# PPGColle.net
KiCad netlist of a schematic drawn in Altium Designer
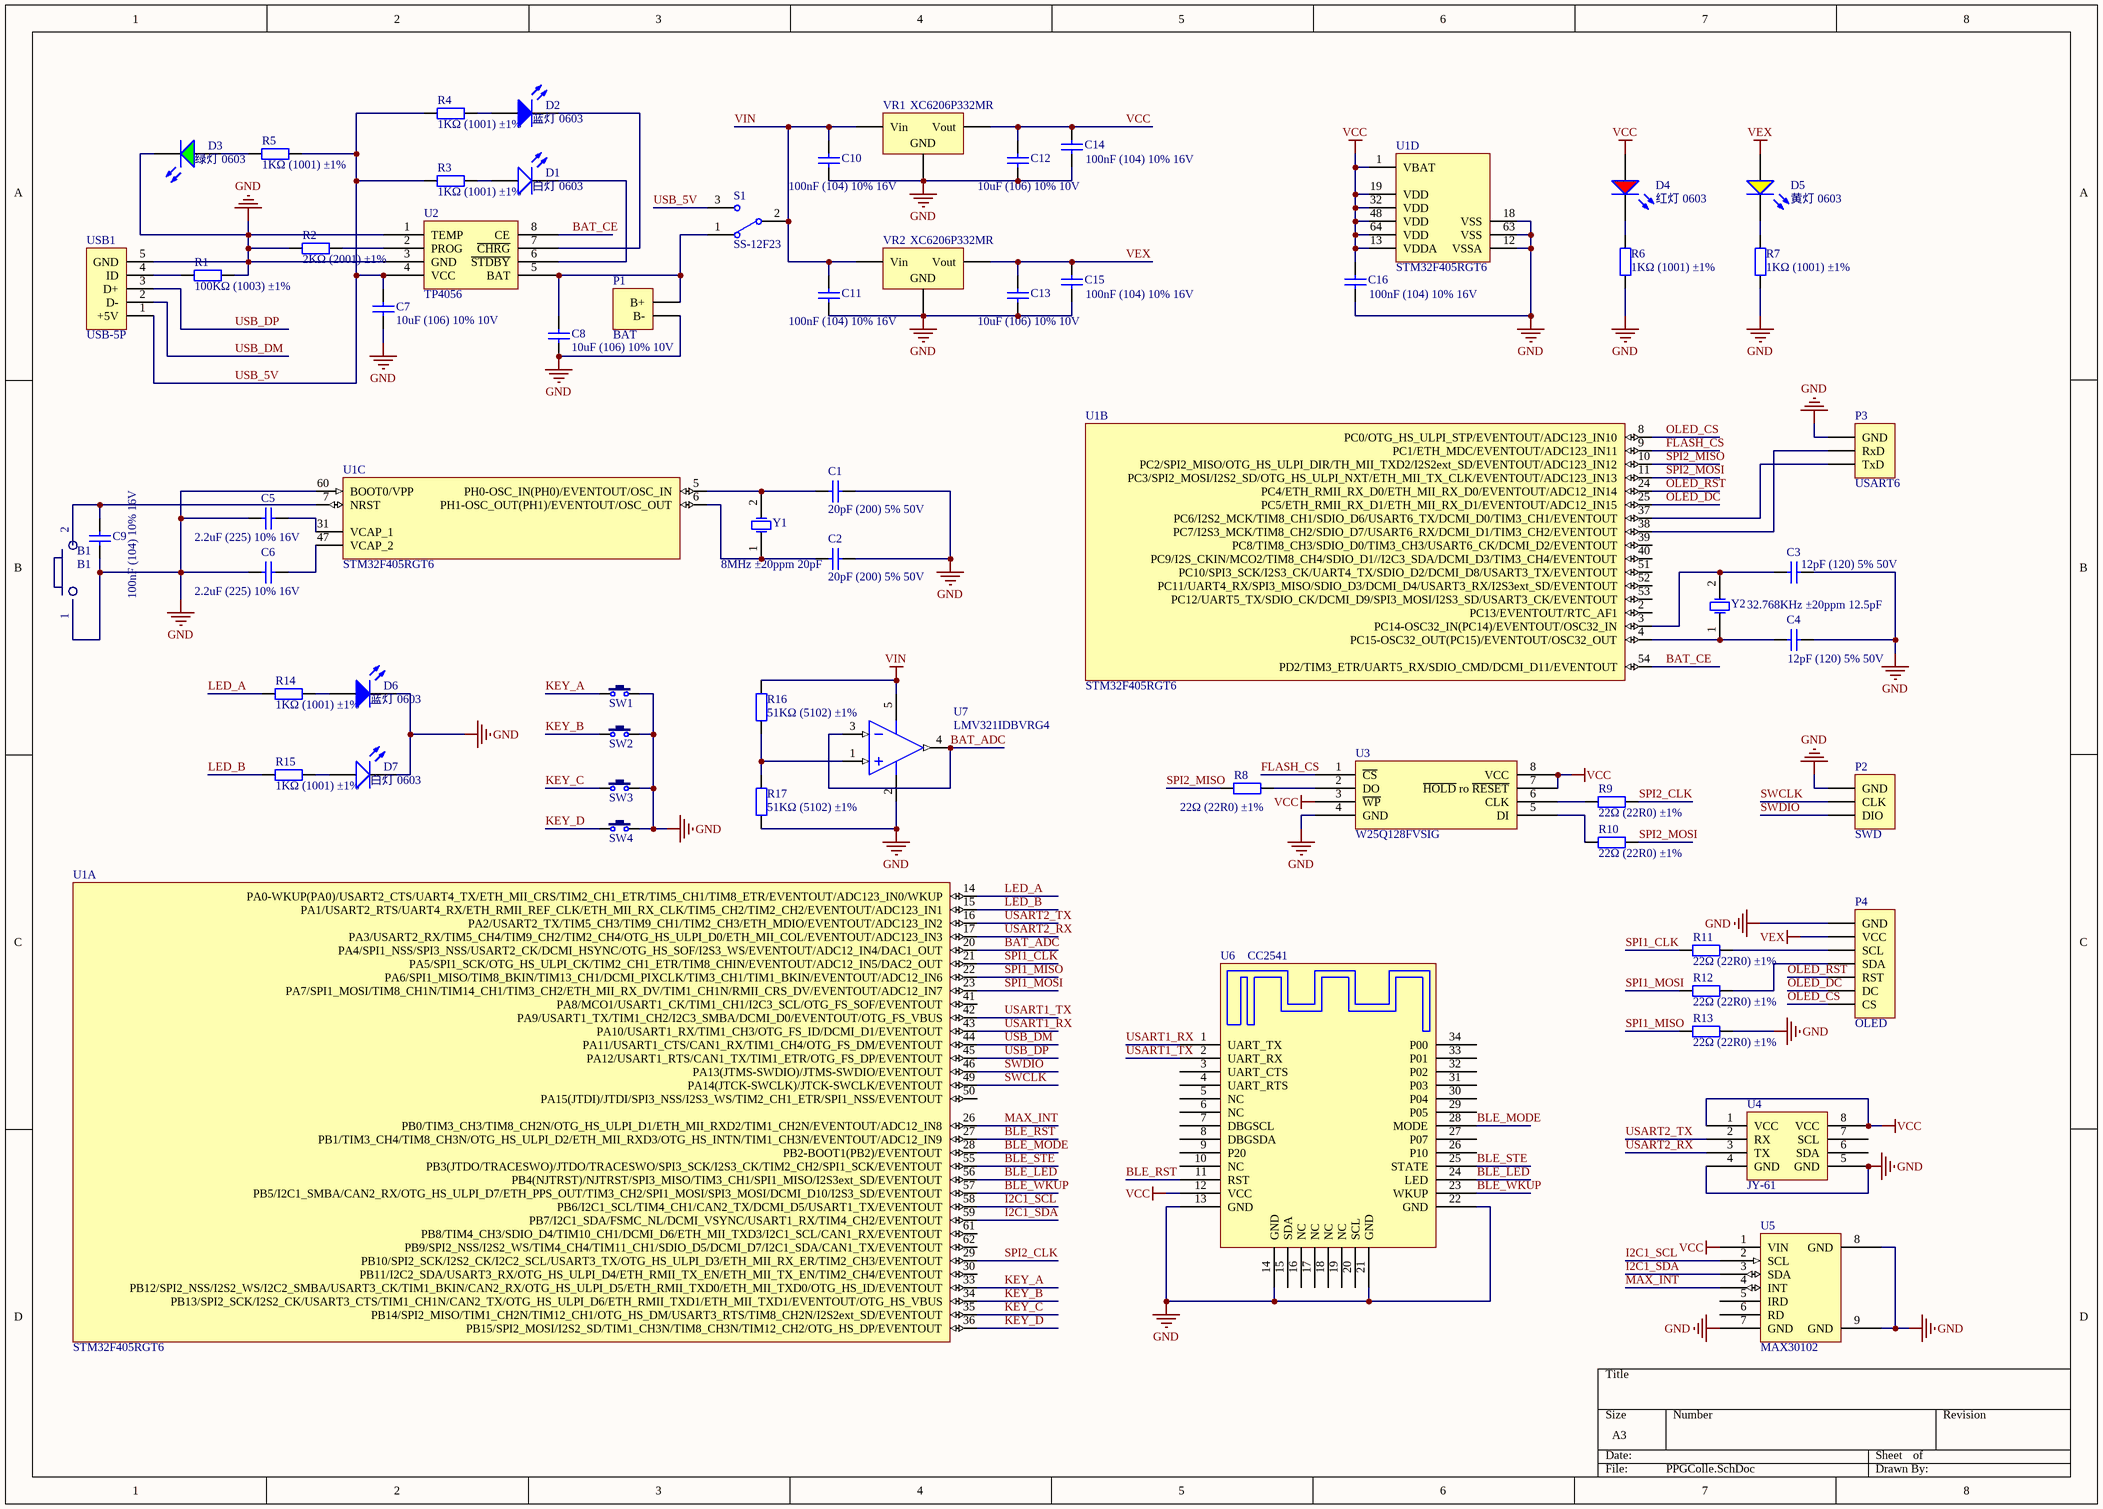
[diagram p0: PPGColle.SchDoc]

(export (version "E")
  (design (tool "Eeschema 10.0.6"))
  (components
    (comp (ref "B1")
      (value "B1")
      (footprint "MetalButton")
      (libsource (lib "MetalButton") (part "MetalButton"))
    )
    (comp (ref "C1")
      (value "20pF (200) 5% 50V")
      (footprint "0402_C")
      (description "贴片电容")
      (libsource (lib "Miscellaneous Devices LC") (part "0402 20pF (200) 5% 50V"))
    )
    (comp (ref "C2")
      (value "20pF (200) 5% 50V")
      (footprint "0402_C")
      (description "贴片电容")
      (libsource (lib "Miscellaneous Devices LC") (part "0402 20pF (200) 5% 50V"))
    )
    (comp (ref "C3")
      (value "12pF (120) 5% 50V")
      (footprint "0402_C")
      (description "贴片电容")
      (libsource (lib "Miscellaneous Devices LC") (part "0402 12pF (120) 5% 50V"))
    )
    (comp (ref "C4")
      (value "12pF (120) 5% 50V")
      (footprint "0402_C")
      (description "贴片电容")
      (libsource (lib "Miscellaneous Devices LC") (part "0402 12pF (120) 5% 50V"))
    )
    (comp (ref "C5")
      (value "2.2uF (225) 10% 16V")
      (footprint "0603_C")
      (description "贴片电容")
      (libsource (lib "Miscellaneous Devices LC") (part "0603 2.2uF (225) 10% 16V"))
    )
    (comp (ref "C6")
      (value "2.2uF (225) 10% 16V")
      (footprint "0603_C")
      (description "贴片电容")
      (libsource (lib "Miscellaneous Devices LC") (part "0603 2.2uF (225) 10% 16V"))
    )
    (comp (ref "C7")
      (value "10uF (106) 10% 10V")
      (footprint "0603_C")
      (description "贴片电容")
      (libsource (lib "Miscellaneous Devices LC") (part "0603 10uF (106) 10% 10V"))
    )
    (comp (ref "C8")
      (value "10uF (106) 10% 10V")
      (footprint "0603_C")
      (description "贴片电容")
      (libsource (lib "Miscellaneous Devices LC") (part "0603 10uF (106) 10% 10V"))
    )
    (comp (ref "C9")
      (value "100nF (104) 10% 16V")
      (footprint "0402_C")
      (description "贴片电容")
      (libsource (lib "Miscellaneous Devices LC") (part "0402 100nF (104) 10% 16V"))
    )
    (comp (ref "C10")
      (value "100nF (104) 10% 16V")
      (footprint "0402_C")
      (description "贴片电容")
      (libsource (lib "Miscellaneous Devices LC") (part "0402 100nF (104) 10% 16V"))
    )
    (comp (ref "C11")
      (value "100nF (104) 10% 16V")
      (footprint "0402_C")
      (description "贴片电容")
      (libsource (lib "Miscellaneous Devices LC") (part "0402 100nF (104) 10% 16V"))
    )
    (comp (ref "C12")
      (value "10uF (106) 10% 10V")
      (footprint "0603_C")
      (description "贴片电容")
      (libsource (lib "Miscellaneous Devices LC") (part "0603 10uF (106) 10% 10V"))
    )
    (comp (ref "C13")
      (value "10uF (106) 10% 10V")
      (footprint "0603_C")
      (description "贴片电容")
      (libsource (lib "Miscellaneous Devices LC") (part "0603 10uF (106) 10% 10V"))
    )
    (comp (ref "C14")
      (value "100nF (104) 10% 16V")
      (footprint "0402_C")
      (description "贴片电容")
      (libsource (lib "Miscellaneous Devices LC") (part "0402 100nF (104) 10% 16V"))
    )
    (comp (ref "C15")
      (value "100nF (104) 10% 16V")
      (footprint "0402_C")
      (description "贴片电容")
      (libsource (lib "Miscellaneous Devices LC") (part "0402 100nF (104) 10% 16V"))
    )
    (comp (ref "C16")
      (value "100nF (104) 10% 16V")
      (footprint "0402_C")
      (description "贴片电容")
      (libsource (lib "Miscellaneous Devices LC") (part "0402 100nF (104) 10% 16V"))
    )
    (comp (ref "D1")
      (value "白灯 0603")
      (footprint "0603_LED_S1")
      (description "发光二极管")
      (libsource (lib "Miscellaneous Devices LC") (part "0603 白灯"))
    )
    (comp (ref "D2")
      (value "蓝灯 0603")
      (footprint "0603_LED_S1")
      (description "发光二极管")
      (libsource (lib "Miscellaneous Devices LC") (part "0603 蓝灯"))
    )
    (comp (ref "D3")
      (value "绿灯 0603")
      (footprint "0603_LED_S1")
      (description "发光二极管")
      (libsource (lib "Miscellaneous Devices LC") (part "0603 绿灯"))
    )
    (comp (ref "D4")
      (value "红灯 0603")
      (footprint "0603_LED_S1")
      (description "发光二极管")
      (libsource (lib "Miscellaneous Devices LC") (part "0603 红灯"))
    )
    (comp (ref "D5")
      (value "黄灯 0603")
      (footprint "0603_LED_S1")
      (description "发光二极管")
      (libsource (lib "Miscellaneous Devices LC") (part "0603 黄灯"))
    )
    (comp (ref "D6")
      (value "蓝灯 0603")
      (footprint "0603_LED_S1")
      (description "发光二极管")
      (libsource (lib "Miscellaneous Devices LC") (part "0603 蓝灯"))
    )
    (comp (ref "D7")
      (value "白灯 0603")
      (footprint "0603_LED_S1")
      (description "发光二极管")
      (libsource (lib "Miscellaneous Devices LC") (part "0603 白灯"))
    )
    (comp (ref "P1")
      (value "BAT")
      (footprint "HDR1X2")
      (description "Header, 2-Pin")
      (fields (field (name "PUBLISHER") "Altium Limited"))
      (libsource (lib "Miscellaneous Connectors") (part "Header 2"))
    )
    (comp (ref "P2")
      (value "SWD")
      (footprint "HDR1X3H")
      (description "Header, 3-Pin, Right Angle")
      (fields (field (name "PUBLISHER") "Altium Limited"))
      (libsource (lib "Miscellaneous Connectors") (part "Header 3H"))
    )
    (comp (ref "P3")
      (value "USART6")
      (footprint "HDR1X3H")
      (description "Header, 3-Pin, Right Angle")
      (fields (field (name "PUBLISHER") "Altium Limited"))
      (libsource (lib "Miscellaneous Connectors") (part "Header 3H"))
    )
    (comp (ref "P4")
      (value "OLED")
      (footprint "HDR1X7")
      (description "Header, 7-Pin")
      (fields (field (name "PUBLISHER") "Altium Limited"))
      (libsource (lib "Miscellaneous Connectors") (part "Header 7"))
    )
    (comp (ref "R1")
      (value "100KΩ (1003) ±1%")
      (footprint "0402_R")
      (description "贴片电阻")
      (libsource (lib "Miscellaneous Devices LC") (part "0402 100KΩ (1003) 1%"))
    )
    (comp (ref "R2")
      (value "2KΩ (2001) ±1%")
      (footprint "0402_R")
      (description "贴片电阻")
      (libsource (lib "Miscellaneous Devices LC") (part "0402 2KΩ (2001) 1%"))
    )
    (comp (ref "R3")
      (value "1KΩ (1001) ±1%")
      (footprint "0402_R")
      (description "贴片电阻")
      (libsource (lib "Miscellaneous Devices LC") (part "0402 1KΩ (1001) 1%"))
    )
    (comp (ref "R4")
      (value "1KΩ (1001) ±1%")
      (footprint "0402_R")
      (description "贴片电阻")
      (libsource (lib "Miscellaneous Devices LC") (part "0402 1KΩ (1001) 1%"))
    )
    (comp (ref "R5")
      (value "1KΩ (1001) ±1%")
      (footprint "0402_R")
      (description "贴片电阻")
      (libsource (lib "Miscellaneous Devices LC") (part "0402 1KΩ (1001) 1%"))
    )
    (comp (ref "R6")
      (value "1KΩ (1001) ±1%")
      (footprint "0402_R")
      (description "贴片电阻")
      (libsource (lib "") (part "0402 1KΩ (1001) 1%_1"))
    )
    (comp (ref "R7")
      (value "1KΩ (1001) ±1%")
      (footprint "0402_R")
      (description "贴片电阻")
      (libsource (lib "") (part "0402 1KΩ (1001) 1%_1"))
    )
    (comp (ref "R8")
      (value "22Ω (22R0) ±1%")
      (footprint "0402_R")
      (description "贴片电阻")
      (libsource (lib "Miscellaneous Devices LC") (part "0402 22Ω (22R0) 1%"))
    )
    (comp (ref "R9")
      (value "22Ω (22R0) ±1%")
      (footprint "0402_R")
      (description "贴片电阻")
      (libsource (lib "Miscellaneous Devices LC") (part "0402 22Ω (22R0) 1%"))
    )
    (comp (ref "R10")
      (value "22Ω (22R0) ±1%")
      (footprint "0402_R")
      (description "贴片电阻")
      (libsource (lib "Miscellaneous Devices LC") (part "0402 22Ω (22R0) 1%"))
    )
    (comp (ref "R11")
      (value "22Ω (22R0) ±1%")
      (footprint "0402_R")
      (description "贴片电阻")
      (libsource (lib "Miscellaneous Devices LC") (part "0402 22Ω (22R0) 1%"))
    )
    (comp (ref "R12")
      (value "22Ω (22R0) ±1%")
      (footprint "0402_R")
      (description "贴片电阻")
      (libsource (lib "Miscellaneous Devices LC") (part "0402 22Ω (22R0) 1%"))
    )
    (comp (ref "R13")
      (value "22Ω (22R0) ±1%")
      (footprint "0402_R")
      (description "贴片电阻")
      (libsource (lib "Miscellaneous Devices LC") (part "0402 22Ω (22R0) 1%"))
    )
    (comp (ref "R14")
      (value "1KΩ (1001) ±1%")
      (footprint "0402_R")
      (description "贴片电阻")
      (libsource (lib "Miscellaneous Devices LC") (part "0402 1KΩ (1001) 1%"))
    )
    (comp (ref "R15")
      (value "1KΩ (1001) ±1%")
      (footprint "0402_R")
      (description "贴片电阻")
      (libsource (lib "Miscellaneous Devices LC") (part "0402 1KΩ (1001) 1%"))
    )
    (comp (ref "R16")
      (value "51KΩ (5102) ±1%")
      (footprint "0402_R")
      (description "贴片电阻")
      (libsource (lib "Miscellaneous Devices LC") (part "0402 51KΩ (5102) 1%"))
    )
    (comp (ref "R17")
      (value "51KΩ (5102) ±1%")
      (footprint "0402_R")
      (description "贴片电阻")
      (libsource (lib "Miscellaneous Devices LC") (part "0402 51KΩ (5102) 1%"))
    )
    (comp (ref "S1")
      (value "SS-12F23")
      (footprint "SS-12F23")
      (description "1路波动开关")
      (fields (field (name "版权归属") "源创客"))
      (libsource (lib "5.1   - 按键-开关") (part "SSW-1P"))
    )
    (comp (ref "SW1")
      (value "3x6x5")
      (footprint "TSW SMD-3*6*4.3")
      (description "3x6轻触开关")
      (fields (field (name "版权归属") "源创客"))
      (libsource (lib "5.1   - 按键-开关") (part "TSW 3x6"))
    )
    (comp (ref "SW2")
      (value "3x6x5")
      (footprint "TSW SMD-3*6*4.3")
      (description "3x6轻触开关")
      (fields (field (name "版权归属") "源创客"))
      (libsource (lib "5.1   - 按键-开关") (part "TSW 3x6"))
    )
    (comp (ref "SW3")
      (value "3x6x5")
      (footprint "TSW SMD-3*6*4.3")
      (description "3x6轻触开关")
      (fields (field (name "版权归属") "源创客"))
      (libsource (lib "5.1   - 按键-开关") (part "TSW 3x6"))
    )
    (comp (ref "SW4")
      (value "3x6x5")
      (footprint "TSW SMD-3*6*4.3")
      (description "3x6轻触开关")
      (fields (field (name "版权归属") "源创客"))
      (libsource (lib "5.1   - 按键-开关") (part "TSW 3x6"))
    )
    (comp (ref "U1")
      (value "STM32F405RGT6")
      (footprint "LQFP-64_10x10x05P")
      (description "ARM")
      (libsource (lib "Miscellaneous Devices LC") (part "STM32F405RGT6"))
    )
    (comp (ref "U2")
      (value "TP4056")
      (footprint "SOP-8_EP_150mil")
      (description "电池电源管理")
      (libsource (lib "Miscellaneous Devices LC") (part "TP4056_[C16581]"))
    )
    (comp (ref "U3")
      (value "W25Q128FVSIG")
      (footprint "SOIC-8_208mil")
      (description "Flash ROM")
      (libsource (lib "Miscellaneous Devices LC") (part "W25Q128FVSIG_[C35101]"))
    )
    (comp (ref "U4")
      (value "JY-61")
      (footprint "JYModulePCB:JY-61")
      (libsource (lib "JYModule") (part "JY-61"))
    )
    (comp (ref "U5") (value "MAX30102") (footprint "MAX30102") (libsource (lib "MAX30102") (part "MAX30102")))
    (comp (ref "U6") (value "CC2541") (footprint "CC2541") (libsource (lib "CC2541") (part "CC2541")))
    (comp (ref "U7")
      (value "LMV321IDBVRG4")
      (footprint "SOT-23-5")
      (description "运放")
      (libsource (lib "Miscellaneous Devices LC") (part "LMV321IDBVRG4_[C7972]"))
    )
    (comp (ref "USB1")
      (value "USB-5P")
      (footprint "USB-MICRO_D")
      (description "微型USB母座")
      (fields (field (name "版权归属") "源创客"))
      (libsource (lib "4.1   - 接口类") (part "USB-5P"))
    )
    (comp (ref "VR1")
      (value "XC6206P332MR")
      (footprint "SOT-23-3L")
      (description "低压差线性稳压(LDO)")
      (libsource (lib "Miscellaneous Devices LC") (part "SOT-23 XC6206P332MR"))
    )
    (comp (ref "VR2")
      (value "XC6206P332MR")
      (footprint "SOT-23-3L")
      (description "低压差线性稳压(LDO)")
      (libsource (lib "Miscellaneous Devices LC") (part "SOT-23 XC6206P332MR"))
    )
    (comp (ref "Y1")
      (value "8MHz ±20ppm 20pF")
      (footprint "SMD-5032_2P")
      (description "贴片晶振")
      (libsource (lib "Miscellaneous Devices LC") (part "SMD-5032_2P 8MHz 20ppm 20pF"))
    )
    (comp (ref "Y2")
      (value "32.768KHz ±20ppm 12.5pF")
      (footprint "SMD-3215_2P FC - 135")
      (description "贴片晶振")
      (libsource (lib "Miscellaneous Devices LC") (part "SMD-3215_2P 32.768KHz 20ppm 12.5pF"))
    )
  )
  (nets
    (net (code "1") (name "/BAT_ADC") (class "Default")
      (node (ref "U1") (pin "20") (pinfunction "PA4/SPI1_NSS/SPI3_NSS/USART2_CK/DCMI_HSYNC/OTG_HS_SOF/I2S3_WS/EVENTOUT/ADC12_IN4/DAC1_OUT_20") (pintype "bidirectional"))
      (node (ref "U7") (pin "3") (pinfunction "IN-_3") (pintype "input"))
      (node (ref "U7") (pin "4") (pinfunction "OUT_4") (pintype "output"))
    )
    (net (code "2") (name "/BAT_CE") (class "Default")
      (node (ref "U1") (pin "54") (pinfunction "PD2/TIM3_ETR/UART5_RX/SDIO_CMD/DCMI_D11/EVENTOUT_54") (pintype "bidirectional"))
      (node (ref "U2") (pin "8") (pinfunction "CE_8") (pintype "passive"))
    )
    (net (code "3") (name "/BLE_LED") (class "Default")
      (node (ref "U1") (pin "56") (pinfunction "PB4(NJTRST)/NJTRST/SPI3_MISO/TIM3_CH1/SPI1_MISO/I2S3ext_SD/EVENTOUT_56") (pintype "bidirectional"))
      (node (ref "U6") (pin "24") (pinfunction "LED_24") (pintype "passive"))
    )
    (net (code "4") (name "/BLE_MODE") (class "Default")
      (node (ref "U1") (pin "28") (pinfunction "PB2-BOOT1(PB2)/EVENTOUT_28") (pintype "bidirectional"))
      (node (ref "U6") (pin "28") (pinfunction "MODE_28") (pintype "passive"))
    )
    (net (code "5") (name "/BLE_RST") (class "Default")
      (node (ref "U1") (pin "27") (pinfunction "PB1/TIM3_CH4/TIM8_CH3N/OTG_HS_ULPI_D2/ETH_MII_RXD3/OTG_HS_INTN/TIM1_CH3N/EVENTOUT/ADC12_IN9_27") (pintype "bidirectional"))
      (node (ref "U6") (pin "11") (pinfunction "RST_11") (pintype "passive"))
    )
    (net (code "6") (name "/BLE_STE") (class "Default")
      (node (ref "U1") (pin "55") (pinfunction "PB3(JTDO/TRACESWO)/JTDO/TRACESWO/SPI3_SCK/I2S3_CK/TIM2_CH2/SPI1_SCK/EVENTOUT_55") (pintype "bidirectional"))
      (node (ref "U6") (pin "25") (pinfunction "STATE_25") (pintype "passive"))
    )
    (net (code "7") (name "/BLE_WKUP") (class "Default")
      (node (ref "U1") (pin "57") (pinfunction "PB5/I2C1_SMBA/CAN2_RX/OTG_HS_ULPI_D7/ETH_PPS_OUT/TIM3_CH2/SPI1_MOSI/SPI3_MOSI/DCMI_D10/I2S3_SD/EVENTOUT_57") (pintype "bidirectional"))
      (node (ref "U6") (pin "23") (pinfunction "WKUP_23") (pintype "passive"))
    )
    (net (code "8") (name "/FLASH_CS") (class "Default")
      (node (ref "U1") (pin "9") (pinfunction "PC1/ETH_MDC/EVENTOUT/ADC123_IN11_9") (pintype "bidirectional"))
      (node (ref "U3") (pin "1") (pinfunction "~{CS}_1") (pintype "passive"))
    )
    (net (code "9") (name "/I2C1_SCL") (class "Default")
      (node (ref "U1") (pin "58") (pinfunction "PB6/I2C1_SCL/TIM4_CH1/CAN2_TX/DCMI_D5/USART1_TX/EVENTOUT_58") (pintype "bidirectional"))
      (node (ref "U5") (pin "2") (pinfunction "SCL_2") (pintype "input"))
    )
    (net (code "10") (name "/I2C1_SDA") (class "Default")
      (node (ref "U1") (pin "59") (pinfunction "PB7/I2C1_SDA/FSMC_NL/DCMI_VSYNC/USART1_RX/TIM4_CH2/EVENTOUT_59") (pintype "bidirectional"))
      (node (ref "U5") (pin "3") (pinfunction "SDA_3") (pintype "bidirectional"))
    )
    (net (code "11") (name "/KEY_A") (class "Default")
      (node (ref "SW1") (pin "1") (pinfunction "1_1") (pintype "passive"))
      (node (ref "U1") (pin "33") (pinfunction "PB12/SPI2_NSS/I2S2_WS/I2C2_SMBA/USART3_CK/TIM1_BKIN/CAN2_RX/OTG_HS_ULPI_D5/ETH_RMII_TXD0/ETH_MII_TXD0/OTG_HS_ID/EVENTOUT_33") (pintype "bidirectional"))
    )
    (net (code "12") (name "/KEY_B") (class "Default")
      (node (ref "SW2") (pin "1") (pinfunction "1_1") (pintype "passive"))
      (node (ref "U1") (pin "34") (pinfunction "PB13/SPI2_SCK/I2S2_CK/USART3_CTS/TIM1_CH1N/CAN2_TX/OTG_HS_ULPI_D6/ETH_RMII_TXD1/ETH_MII_TXD1/EVENTOUT/OTG_HS_VBUS_34") (pintype "bidirectional"))
    )
    (net (code "13") (name "/KEY_C") (class "Default")
      (node (ref "SW3") (pin "1") (pinfunction "1_1") (pintype "passive"))
      (node (ref "U1") (pin "35") (pinfunction "PB14/SPI2_MISO/TIM1_CH2N/TIM12_CH1/OTG_HS_DM/USART3_RTS/TIM8_CH2N/I2S2ext_SD/EVENTOUT_35") (pintype "bidirectional"))
    )
    (net (code "14") (name "/KEY_D") (class "Default")
      (node (ref "SW4") (pin "1") (pinfunction "1_1") (pintype "passive"))
      (node (ref "U1") (pin "36") (pinfunction "PB15/SPI2_MOSI/I2S2_SD/TIM1_CH3N/TIM8_CH3N/TIM12_CH2/OTG_HS_DP/EVENTOUT_36") (pintype "bidirectional"))
    )
    (net (code "15") (name "/LED_A") (class "Default")
      (node (ref "R14") (pin "2") (pinfunction "2_2") (pintype "passive"))
      (node (ref "U1") (pin "14") (pinfunction "PA0-WKUP(PA0)/USART2_CTS/UART4_TX/ETH_MII_CRS/TIM2_CH1_ETR/TIM5_CH1/TIM8_ETR/EVENTOUT/ADC123_IN0/WKUP_14") (pintype "bidirectional"))
    )
    (net (code "16") (name "/LED_B") (class "Default")
      (node (ref "R15") (pin "2") (pinfunction "2_2") (pintype "passive"))
      (node (ref "U1") (pin "15") (pinfunction "PA1/USART2_RTS/UART4_RX/ETH_RMII_REF_CLK/ETH_MII_RX_CLK/TIM5_CH2/TIM2_CH2/EVENTOUT/ADC123_IN1_15") (pintype "bidirectional"))
    )
    (net (code "17") (name "/MAX_INT") (class "Default")
      (node (ref "U1") (pin "26") (pinfunction "PB0/TIM3_CH3/TIM8_CH2N/OTG_HS_ULPI_D1/ETH_MII_RXD2/TIM1_CH2N/EVENTOUT/ADC12_IN8_26") (pintype "bidirectional"))
      (node (ref "U5") (pin "4") (pinfunction "INT_4") (pintype "bidirectional"))
    )
    (net (code "18") (name "/OLED_CS") (class "Default")
      (node (ref "P4") (pin "7") (pinfunction "CS_7") (pintype "passive"))
      (node (ref "U1") (pin "8") (pinfunction "PC0/OTG_HS_ULPI_STP/EVENTOUT/ADC123_IN10_8") (pintype "bidirectional"))
    )
    (net (code "19") (name "/OLED_DC") (class "Default")
      (node (ref "P4") (pin "6") (pinfunction "DC_6") (pintype "passive"))
      (node (ref "U1") (pin "25") (pinfunction "PC5/ETH_RMII_RX_D1/ETH_MII_RX_D1/EVENTOUT/ADC12_IN15_25") (pintype "bidirectional"))
    )
    (net (code "20") (name "/OLED_RST") (class "Default")
      (node (ref "P4") (pin "5") (pinfunction "RST_5") (pintype "passive"))
      (node (ref "U1") (pin "24") (pinfunction "PC4/ETH_RMII_RX_D0/ETH_MII_RX_D0/EVENTOUT/ADC12_IN14_24") (pintype "bidirectional"))
    )
    (net (code "21") (name "/SPI1_CLK") (class "Default")
      (node (ref "R11") (pin "1") (pinfunction "1_1") (pintype "passive"))
      (node (ref "U1") (pin "21") (pinfunction "PA5/SPI1_SCK/OTG_HS_ULPI_CK/TIM2_CH1_ETR/TIM8_CHIN/EVENTOUT/ADC12_IN5/DAC2_OUT_21") (pintype "bidirectional"))
    )
    (net (code "22") (name "/SPI1_MISO") (class "Default")
      (node (ref "R13") (pin "1") (pinfunction "1_1") (pintype "passive"))
      (node (ref "U1") (pin "22") (pinfunction "PA6/SPI1_MISO/TIM8_BKIN/TIM13_CH1/DCMI_PIXCLK/TIM3_CH1/TIM1_BKIN/EVENTOUT/ADC12_IN6_22") (pintype "bidirectional"))
    )
    (net (code "23") (name "/SPI1_MOSI") (class "Default")
      (node (ref "R12") (pin "1") (pinfunction "1_1") (pintype "passive"))
      (node (ref "U1") (pin "23") (pinfunction "PA7/SPI1_MOSI/TIM8_CH1N/TIM14_CH1/TIM3_CH2/ETH_MII_RX_DV/TIM1_CH1N/RMII_CRS_DV/EVENTOUT/ADC12_IN7_23") (pintype "bidirectional"))
    )
    (net (code "24") (name "/SPI2_CLK") (class "Default")
      (node (ref "R9") (pin "2") (pinfunction "2_2") (pintype "passive"))
      (node (ref "U1") (pin "29") (pinfunction "PB10/SPI2_SCK/I2S2_CK/I2C2_SCL/USART3_TX/OTG_HS_ULPI_D3/ETH_MII_RX_ER/TIM2_CH3/EVENTOUT_29") (pintype "bidirectional"))
    )
    (net (code "25") (name "/SPI2_MISO") (class "Default")
      (node (ref "R8") (pin "1") (pinfunction "1_1") (pintype "passive"))
      (node (ref "U1") (pin "10") (pinfunction "PC2/SPI2_MISO/OTG_HS_ULPI_DIR/TH_MII_TXD2/I2S2ext_SD/EVENTOUT/ADC123_IN12_10") (pintype "bidirectional"))
    )
    (net (code "26") (name "/SPI2_MOSI") (class "Default")
      (node (ref "R10") (pin "2") (pinfunction "2_2") (pintype "passive"))
      (node (ref "U1") (pin "11") (pinfunction "PC3/SPI2_MOSI/I2S2_SD/OTG_HS_ULPI_NXT/ETH_MII_TX_CLK/EVENTOUT/ADC123_IN13_11") (pintype "bidirectional"))
    )
    (net (code "27") (name "/SWCLK") (class "Default")
      (node (ref "P2") (pin "2") (pinfunction "CLK_2") (pintype "passive"))
      (node (ref "U1") (pin "49") (pinfunction "PA14(JTCK-SWCLK)/JTCK-SWCLK/EVENTOUT_49") (pintype "bidirectional"))
    )
    (net (code "28") (name "/SWDIO") (class "Default")
      (node (ref "P2") (pin "3") (pinfunction "DIO_3") (pintype "passive"))
      (node (ref "U1") (pin "46") (pinfunction "PA13(JTMS-SWDIO)/JTMS-SWDIO/EVENTOUT_46") (pintype "bidirectional"))
    )
    (net (code "29") (name "/USART1_RX") (class "Default")
      (node (ref "U1") (pin "43") (pinfunction "PA10/USART1_RX/TIM1_CH3/OTG_FS_ID/DCMI_D1/EVENTOUT_43") (pintype "bidirectional"))
      (node (ref "U6") (pin "1") (pinfunction "UART_TX_1") (pintype "passive"))
    )
    (net (code "30") (name "/USART1_TX") (class "Default")
      (node (ref "U1") (pin "42") (pinfunction "PA9/USART1_TX/TIM1_CH2/I2C3_SMBA/DCMI_D0/EVENTOUT/OTG_FS_VBUS_42") (pintype "bidirectional"))
      (node (ref "U6") (pin "2") (pinfunction "UART_RX_2") (pintype "passive"))
    )
    (net (code "31") (name "/USART2_RX") (class "Default")
      (node (ref "U1") (pin "17") (pinfunction "PA3/USART2_RX/TIM5_CH4/TIM9_CH2/TIM2_CH4/OTG_HS_ULPI_D0/ETH_MII_COL/EVENTOUT/ADC123_IN3_17") (pintype "bidirectional"))
      (node (ref "U4") (pin "3") (pinfunction "TX_3") (pintype "passive"))
    )
    (net (code "32") (name "/USART2_TX") (class "Default")
      (node (ref "U1") (pin "16") (pinfunction "PA2/USART2_TX/TIM5_CH3/TIM9_CH1/TIM2_CH3/ETH_MDIO/EVENTOUT/ADC123_IN2_16") (pintype "bidirectional"))
      (node (ref "U4") (pin "2") (pinfunction "RX_2") (pintype "passive"))
    )
    (net (code "33") (name "/USB_5V") (class "Default")
      (node (ref "C7") (pin "2") (pinfunction "2_2") (pintype "passive"))
      (node (ref "R3") (pin "2") (pinfunction "2_2") (pintype "passive"))
      (node (ref "R4") (pin "2") (pinfunction "2_2") (pintype "passive"))
      (node (ref "R5") (pin "1") (pinfunction "1_1") (pintype "passive"))
      (node (ref "S1") (pin "3") (pinfunction "3_3") (pintype "passive"))
      (node (ref "U2") (pin "4") (pinfunction "VCC_4") (pintype "passive"))
      (node (ref "USB1") (pin "1") (pinfunction "+5V_1") (pintype "passive"))
    )
    (net (code "34") (name "/USB_DM") (class "Default")
      (node (ref "U1") (pin "44") (pinfunction "PA11/USART1_CTS/CAN1_RX/TIM1_CH4/OTG_FS_DM/EVENTOUT_44") (pintype "bidirectional"))
      (node (ref "USB1") (pin "2") (pinfunction "D-_2") (pintype "passive"))
    )
    (net (code "35") (name "/USB_DP") (class "Default")
      (node (ref "U1") (pin "45") (pinfunction "PA12/USART1_RTS/CAN1_TX/TIM1_ETR/OTG_FS_DP/EVENTOUT_45") (pintype "bidirectional"))
      (node (ref "USB1") (pin "3") (pinfunction "D+_3") (pintype "passive"))
    )
    (net (code "36") (name "GND") (class "Default")
      (node (ref "B1") (pin "1") (pinfunction "1_1") (pintype "passive"))
      (node (ref "C1") (pin "2") (pinfunction "2_2") (pintype "passive"))
      (node (ref "C10") (pin "1") (pinfunction "1_1") (pintype "passive"))
      (node (ref "C11") (pin "1") (pinfunction "1_1") (pintype "passive"))
      (node (ref "C12") (pin "2") (pinfunction "2_2") (pintype "passive"))
      (node (ref "C13") (pin "2") (pinfunction "2_2") (pintype "passive"))
      (node (ref "C14") (pin "1") (pinfunction "1_1") (pintype "passive"))
      (node (ref "C15") (pin "1") (pinfunction "1_1") (pintype "passive"))
      (node (ref "C16") (pin "1") (pinfunction "1_1") (pintype "passive"))
      (node (ref "C2") (pin "2") (pinfunction "2_2") (pintype "passive"))
      (node (ref "C3") (pin "2") (pinfunction "2_2") (pintype "passive"))
      (node (ref "C4") (pin "2") (pinfunction "2_2") (pintype "passive"))
      (node (ref "C5") (pin "1") (pinfunction "1_1") (pintype "passive"))
      (node (ref "C6") (pin "1") (pinfunction "1_1") (pintype "passive"))
      (node (ref "C7") (pin "1") (pinfunction "1_1") (pintype "passive"))
      (node (ref "C8") (pin "2") (pinfunction "2_2") (pintype "passive"))
      (node (ref "C9") (pin "1") (pinfunction "1_1") (pintype "passive"))
      (node (ref "D3") (pin "K") (pinfunction "K_K") (pintype "passive"))
      (node (ref "D6") (pin "K") (pinfunction "K_K") (pintype "passive"))
      (node (ref "D7") (pin "K") (pinfunction "K_K") (pintype "passive"))
      (node (ref "P1") (pin "1") (pinfunction "B-_1") (pintype "passive"))
      (node (ref "P2") (pin "1") (pinfunction "GND_1") (pintype "passive"))
      (node (ref "P3") (pin "1") (pinfunction "GND_1") (pintype "passive"))
      (node (ref "P4") (pin "1") (pinfunction "GND_1") (pintype "passive"))
      (node (ref "R1") (pin "2") (pinfunction "2_2") (pintype "passive"))
      (node (ref "R13") (pin "2") (pinfunction "2_2") (pintype "passive"))
      (node (ref "R17") (pin "1") (pinfunction "1_1") (pintype "passive"))
      (node (ref "R2") (pin "1") (pinfunction "1_1") (pintype "passive"))
      (node (ref "R6") (pin "2") (pinfunction "2_2") (pintype "passive"))
      (node (ref "R7") (pin "2") (pinfunction "2_2") (pintype "passive"))
      (node (ref "SW1") (pin "2") (pinfunction "2_2") (pintype "passive"))
      (node (ref "SW2") (pin "2") (pinfunction "2_2") (pintype "passive"))
      (node (ref "SW3") (pin "2") (pinfunction "2_2") (pintype "passive"))
      (node (ref "SW4") (pin "2") (pinfunction "2_2") (pintype "passive"))
      (node (ref "U1") (pin "12") (pinfunction "VSSA_12") (pintype "power_in"))
      (node (ref "U1") (pin "18") (pinfunction "VSS_18") (pintype "power_in"))
      (node (ref "U1") (pin "60") (pinfunction "BOOT0/VPP_60") (pintype "input"))
      (node (ref "U1") (pin "63") (pinfunction "VSS_63") (pintype "power_in"))
      (node (ref "U2") (pin "1") (pinfunction "TEMP_1") (pintype "passive"))
      (node (ref "U2") (pin "3") (pinfunction "GND_3") (pintype "passive"))
      (node (ref "U3") (pin "4") (pinfunction "GND_4") (pintype "passive"))
      (node (ref "U4") (pin "4") (pinfunction "GND_4") (pintype "passive"))
      (node (ref "U4") (pin "5") (pinfunction "GND_5") (pintype "passive"))
      (node (ref "U5") (pin "7") (pinfunction "GND_7") (pintype "power_in"))
      (node (ref "U5") (pin "8") (pinfunction "GND_8") (pintype "passive"))
      (node (ref "U5") (pin "9") (pinfunction "GND_9") (pintype "passive"))
      (node (ref "U6") (pin "13") (pinfunction "GND_13") (pintype "passive"))
      (node (ref "U6") (pin "14") (pinfunction "GND_14") (pintype "passive"))
      (node (ref "U6") (pin "21") (pinfunction "GND_21") (pintype "passive"))
      (node (ref "U6") (pin "22") (pinfunction "GND_22") (pintype "passive"))
      (node (ref "U7") (pin "2") (pinfunction "V-_2") (pintype "power_in"))
      (node (ref "USB1") (pin "5") (pinfunction "GND_5") (pintype "passive"))
      (node (ref "VR1") (pin "1") (pinfunction "GND_1") (pintype "passive"))
      (node (ref "VR2") (pin "1") (pinfunction "GND_1") (pintype "passive"))
    )
    (net (code "37") (name "Net-(D1-PadA)") (class "Default")
      (node (ref "D1") (pin "A") (pinfunction "A_A") (pintype "passive"))
      (node (ref "R3") (pin "1") (pinfunction "1_1") (pintype "passive"))
    )
    (net (code "38") (name "Net-(D2-PadA)") (class "Default")
      (node (ref "D2") (pin "A") (pinfunction "A_A") (pintype "passive"))
      (node (ref "R4") (pin "1") (pinfunction "1_1") (pintype "passive"))
    )
    (net (code "39") (name "Net-(D3-PadA)") (class "Default")
      (node (ref "D3") (pin "A") (pinfunction "A_A") (pintype "passive"))
      (node (ref "R5") (pin "2") (pinfunction "2_2") (pintype "passive"))
    )
    (net (code "40") (name "Net-(D4-PadK)") (class "Default")
      (node (ref "D4") (pin "K") (pinfunction "K_K") (pintype "passive"))
      (node (ref "R6") (pin "1") (pinfunction "1_1") (pintype "passive"))
    )
    (net (code "41") (name "Net-(D5-PadK)") (class "Default")
      (node (ref "D5") (pin "K") (pinfunction "K_K") (pintype "passive"))
      (node (ref "R7") (pin "1") (pinfunction "1_1") (pintype "passive"))
    )
    (net (code "42") (name "Net-(D6-PadA)") (class "Default")
      (node (ref "D6") (pin "A") (pinfunction "A_A") (pintype "passive"))
      (node (ref "R14") (pin "1") (pinfunction "1_1") (pintype "passive"))
    )
    (net (code "43") (name "Net-(D7-PadA)") (class "Default")
      (node (ref "D7") (pin "A") (pinfunction "A_A") (pintype "passive"))
      (node (ref "R15") (pin "1") (pinfunction "1_1") (pintype "passive"))
    )
    (net (code "44") (name "Net-(P1-B+)") (class "Default")
      (node (ref "C8") (pin "1") (pinfunction "1_1") (pintype "passive"))
      (node (ref "P1") (pin "2") (pinfunction "B+_2") (pintype "passive"))
      (node (ref "S1") (pin "1") (pinfunction "1_1") (pintype "passive"))
      (node (ref "U2") (pin "5") (pinfunction "BAT_5") (pintype "passive"))
    )
    (net (code "45") (name "Net-(P3-CLK)") (class "Default")
      (node (ref "P3") (pin "2") (pinfunction "CLK_2") (pintype "passive"))
      (node (ref "U1") (pin "38") (pinfunction "PC7/I2S3_MCK/TIM8_CH2/SDIO_D7/USART6_RX/DCMI_D1/TIM3_CH2/EVENTOUT_38") (pintype "bidirectional"))
    )
    (net (code "46") (name "Net-(P3-DIO)") (class "Default")
      (node (ref "P3") (pin "3") (pinfunction "DIO_3") (pintype "passive"))
      (node (ref "U1") (pin "37") (pinfunction "PC6/I2S2_MCK/TIM8_CH1/SDIO_D6/USART6_TX/DCMI_D0/TIM3_CH1/EVENTOUT_37") (pintype "bidirectional"))
    )
    (net (code "47") (name "Net-(P4-SCL)") (class "Default")
      (node (ref "P4") (pin "3") (pinfunction "SCL_3") (pintype "passive"))
      (node (ref "R11") (pin "2") (pinfunction "2_2") (pintype "passive"))
    )
    (net (code "48") (name "Net-(P4-SDA)") (class "Default")
      (node (ref "P4") (pin "4") (pinfunction "SDA_4") (pintype "passive"))
      (node (ref "R12") (pin "2") (pinfunction "2_2") (pintype "passive"))
    )
    (net (code "49") (name "Net-(U1B-PC14-OSC32_IN(PC14){slash}EVENTOUT{slash}OSC32_IN)") (class "Default")
      (node (ref "C3") (pin "1") (pinfunction "1_1") (pintype "passive"))
      (node (ref "U1") (pin "3") (pinfunction "PC14-OSC32_IN(PC14)/EVENTOUT/OSC32_IN_3") (pintype "bidirectional"))
      (node (ref "Y2") (pin "2") (pinfunction "OSC2_2") (pintype "passive"))
    )
    (net (code "50") (name "Net-(U1B-PC15-OSC32_OUT(PC15){slash}EVENTOUT{slash}OSC32_OUT)") (class "Default")
      (node (ref "C4") (pin "1") (pinfunction "1_1") (pintype "passive"))
      (node (ref "U1") (pin "4") (pinfunction "PC15-OSC32_OUT(PC15)/EVENTOUT/OSC32_OUT_4") (pintype "bidirectional"))
      (node (ref "Y2") (pin "1") (pinfunction "OSC1_1") (pintype "passive"))
    )
    (net (code "51") (name "Net-(U1C-NRST)") (class "Default")
      (node (ref "B1") (pin "2") (pinfunction "2_2") (pintype "passive"))
      (node (ref "C9") (pin "2") (pinfunction "2_2") (pintype "passive"))
      (node (ref "U1") (pin "7") (pinfunction "NRST_7") (pintype "bidirectional"))
    )
    (net (code "52") (name "Net-(U1C-PH0-OSC_IN(PH0){slash}EVENTOUT{slash}OSC_IN)") (class "Default")
      (node (ref "C1") (pin "1") (pinfunction "1_1") (pintype "passive"))
      (node (ref "U1") (pin "5") (pinfunction "PH0-OSC_IN(PH0)/EVENTOUT/OSC_IN_5") (pintype "bidirectional"))
      (node (ref "Y1") (pin "2") (pinfunction "OSC2_2") (pintype "passive"))
    )
    (net (code "53") (name "Net-(U1C-PH1-OSC_OUT(PH1){slash}EVENTOUT{slash}OSC_OUT)") (class "Default")
      (node (ref "C2") (pin "1") (pinfunction "1_1") (pintype "passive"))
      (node (ref "U1") (pin "6") (pinfunction "PH1-OSC_OUT(PH1)/EVENTOUT/OSC_OUT_6") (pintype "bidirectional"))
      (node (ref "Y1") (pin "1") (pinfunction "OSC1_1") (pintype "passive"))
    )
    (net (code "54") (name "Net-(U1C-VCAP_1)") (class "Default")
      (node (ref "C5") (pin "2") (pinfunction "2_2") (pintype "passive"))
      (node (ref "U1") (pin "31") (pinfunction "VCAP_1_31") (pintype "power_in"))
    )
    (net (code "55") (name "Net-(U1C-VCAP_2)") (class "Default")
      (node (ref "C6") (pin "2") (pinfunction "2_2") (pintype "passive"))
      (node (ref "U1") (pin "47") (pinfunction "VCAP_2_47") (pintype "power_in"))
    )
    (net (code "56") (name "Net-(U2-PROG)") (class "Default")
      (node (ref "R2") (pin "2") (pinfunction "2_2") (pintype "passive"))
      (node (ref "U2") (pin "2") (pinfunction "PROG_2") (pintype "passive"))
    )
    (net (code "57") (name "Net-(U2-~{CHRG})") (class "Default")
      (node (ref "D2") (pin "K") (pinfunction "K_K") (pintype "passive"))
      (node (ref "U2") (pin "7") (pinfunction "~{CHRG}_7") (pintype "passive"))
    )
    (net (code "58") (name "Net-(U2-~{STDBY})") (class "Default")
      (node (ref "D1") (pin "K") (pinfunction "K_K") (pintype "passive"))
      (node (ref "U2") (pin "6") (pinfunction "~{STDBY}_6") (pintype "passive"))
    )
    (net (code "59") (name "Net-(U3-CLK)") (class "Default")
      (node (ref "R9") (pin "1") (pinfunction "1_1") (pintype "passive"))
      (node (ref "U3") (pin "6") (pinfunction "CLK_6") (pintype "passive"))
    )
    (net (code "60") (name "Net-(U3-DI)") (class "Default")
      (node (ref "R10") (pin "1") (pinfunction "1_1") (pintype "passive"))
      (node (ref "U3") (pin "5") (pinfunction "DI_5") (pintype "passive"))
    )
    (net (code "61") (name "Net-(U3-DO)") (class "Default")
      (node (ref "R8") (pin "2") (pinfunction "2_2") (pintype "passive"))
      (node (ref "U3") (pin "2") (pinfunction "DO_2") (pintype "passive"))
    )
    (net (code "62") (name "Net-(U7-IN+)") (class "Default")
      (node (ref "R16") (pin "1") (pinfunction "1_1") (pintype "passive"))
      (node (ref "R17") (pin "2") (pinfunction "2_2") (pintype "passive"))
      (node (ref "U7") (pin "1") (pinfunction "IN+_1") (pintype "input"))
    )
    (net (code "63") (name "Net-(USB1-ID)") (class "Default")
      (node (ref "R1") (pin "1") (pinfunction "1_1") (pintype "passive"))
      (node (ref "USB1") (pin "4") (pinfunction "ID_4") (pintype "passive"))
    )
    (net (code "64") (name "VCC") (class "Default")
      (node (ref "C12") (pin "1") (pinfunction "1_1") (pintype "passive"))
      (node (ref "C14") (pin "2") (pinfunction "2_2") (pintype "passive"))
      (node (ref "C16") (pin "2") (pinfunction "2_2") (pintype "passive"))
      (node (ref "D4") (pin "A") (pinfunction "A_A") (pintype "passive"))
      (node (ref "U1") (pin "1") (pinfunction "VBAT_1") (pintype "power_in"))
      (node (ref "U1") (pin "13") (pinfunction "VDDA_13") (pintype "power_in"))
      (node (ref "U1") (pin "19") (pinfunction "VDD_19") (pintype "power_in"))
      (node (ref "U1") (pin "32") (pinfunction "VDD_32") (pintype "power_in"))
      (node (ref "U1") (pin "48") (pinfunction "VDD_48") (pintype "power_in"))
      (node (ref "U1") (pin "64") (pinfunction "VDD_64") (pintype "power_in"))
      (node (ref "U3") (pin "3") (pinfunction "~{WP}_3") (pintype "passive"))
      (node (ref "U3") (pin "7") (pinfunction "~{HOLD}_ro_~{RESET}_7") (pintype "passive"))
      (node (ref "U3") (pin "8") (pinfunction "VCC_8") (pintype "passive"))
      (node (ref "U4") (pin "1") (pinfunction "VCC_1") (pintype "passive"))
      (node (ref "U4") (pin "8") (pinfunction "VCC_8") (pintype "passive"))
      (node (ref "U5") (pin "1") (pinfunction "VIN_1") (pintype "power_in"))
      (node (ref "U6") (pin "12") (pinfunction "VCC_12") (pintype "passive"))
      (node (ref "VR1") (pin "2") (pinfunction "Vout_2") (pintype "passive"))
    )
    (net (code "65") (name "VEX") (class "Default")
      (node (ref "C13") (pin "1") (pinfunction "1_1") (pintype "passive"))
      (node (ref "C15") (pin "2") (pinfunction "2_2") (pintype "passive"))
      (node (ref "D5") (pin "A") (pinfunction "A_A") (pintype "passive"))
      (node (ref "P4") (pin "2") (pinfunction "VCC_2") (pintype "passive"))
      (node (ref "VR2") (pin "2") (pinfunction "Vout_2") (pintype "passive"))
    )
    (net (code "66") (name "VIN") (class "Default")
      (node (ref "C10") (pin "2") (pinfunction "2_2") (pintype "passive"))
      (node (ref "C11") (pin "2") (pinfunction "2_2") (pintype "passive"))
      (node (ref "R16") (pin "2") (pinfunction "2_2") (pintype "passive"))
      (node (ref "S1") (pin "2") (pinfunction "2_2") (pintype "passive"))
      (node (ref "U7") (pin "5") (pinfunction "V+_5") (pintype "power_in"))
      (node (ref "VR1") (pin "3") (pinfunction "Vin_3") (pintype "passive"))
      (node (ref "VR2") (pin "3") (pinfunction "Vin_3") (pintype "passive"))
    )
    (net (code "67") (name "unconnected-(U1A-PA8{slash}MCO1{slash}USART1_CK{slash}TIM1_CH1{slash}I2C3_SCL{slash}OTG_FS_SOF{slash}EVENTOUT-Pad41)") (class "Default")
      (node (ref "U1") (pin "41") (pinfunction "PA8/MCO1/USART1_CK/TIM1_CH1/I2C3_SCL/OTG_FS_SOF/EVENTOUT_41") (pintype "bidirectional"))
    )
    (net (code "68") (name "unconnected-(U1A-PA15(JTDI){slash}JTDI{slash}SPI3_NSS{slash}I2S3_WS{slash}TIM2_CH1_ETR{slash}SPI1_NSS{slash}EVENTOUT-Pad50)") (class "Default")
      (node (ref "U1") (pin "50") (pinfunction "PA15(JTDI)/JTDI/SPI3_NSS/I2S3_WS/TIM2_CH1_ETR/SPI1_NSS/EVENTOUT_50") (pintype "bidirectional"))
    )
    (net (code "69") (name "unconnected-(U1A-PB8{slash}TIM4_CH3{slash}SDIO_D4{slash}TIM10_CH1{slash}DCMI_D6{slash}ETH_MII_TXD3{slash}I2C1_SCL{slash}CAN1_RX{slash}EVENTOUT-Pad61)") (class "Default")
      (node (ref "U1") (pin "61") (pinfunction "PB8/TIM4_CH3/SDIO_D4/TIM10_CH1/DCMI_D6/ETH_MII_TXD3/I2C1_SCL/CAN1_RX/EVENTOUT_61") (pintype "bidirectional"))
    )
    (net (code "70") (name "unconnected-(U1A-PB9{slash}SPI2_NSS{slash}I2S2_WS{slash}TIM4_CH4{slash}TIM11_CH1{slash}SDIO_D5{slash}DCMI_D7{slash}I2C1_SDA{slash}CAN1_TX{slash}EVENTOUT-Pad62)") (class "Default")
      (node (ref "U1") (pin "62") (pinfunction "PB9/SPI2_NSS/I2S2_WS/TIM4_CH4/TIM11_CH1/SDIO_D5/DCMI_D7/I2C1_SDA/CAN1_TX/EVENTOUT_62") (pintype "bidirectional"))
    )
    (net (code "71") (name "unconnected-(U1A-PB11{slash}I2C2_SDA{slash}USART3_RX{slash}OTG_HS_ULPI_D4{slash}ETH_RMII_TX_EN{slash}ETH_MII_TX_EN{slash}TIM2_CH4{slash}EVENTOUT-Pad30)") (class "Default")
      (node (ref "U1") (pin "30") (pinfunction "PB11/I2C2_SDA/USART3_RX/OTG_HS_ULPI_D4/ETH_RMII_TX_EN/ETH_MII_TX_EN/TIM2_CH4/EVENTOUT_30") (pintype "bidirectional"))
    )
    (net (code "72") (name "unconnected-(U1B-PC8{slash}TIM8_CH3{slash}SDIO_D0{slash}TIM3_CH3{slash}USART6_CK{slash}DCMI_D2{slash}EVENTOUT-Pad39)") (class "Default")
      (node (ref "U1") (pin "39") (pinfunction "PC8/TIM8_CH3/SDIO_D0/TIM3_CH3/USART6_CK/DCMI_D2/EVENTOUT_39") (pintype "bidirectional"))
    )
    (net (code "73") (name "unconnected-(U1B-PC9{slash}I2S_CKIN{slash}MCO2{slash}TIM8_CH4{slash}SDIO_D1{slash}{slash}I2C3_SDA{slash}DCMI_D3{slash}TIM3_CH4{slash}EVENTOUT-Pad40)") (class "Default")
      (node (ref "U1") (pin "40") (pinfunction "PC9/I2S_CKIN/MCO2/TIM8_CH4/SDIO_D1//I2C3_SDA/DCMI_D3/TIM3_CH4/EVENTOUT_40") (pintype "bidirectional"))
    )
    (net (code "74") (name "unconnected-(U1B-PC10{slash}SPI3_SCK{slash}I2S3_CK{slash}UART4_TX{slash}SDIO_D2{slash}DCMI_D8{slash}USART3_TX{slash}EVENTOUT-Pad51)") (class "Default")
      (node (ref "U1") (pin "51") (pinfunction "PC10/SPI3_SCK/I2S3_CK/UART4_TX/SDIO_D2/DCMI_D8/USART3_TX/EVENTOUT_51") (pintype "bidirectional"))
    )
    (net (code "75") (name "unconnected-(U1B-PC11{slash}UART4_RX{slash}SPI3_MISO{slash}SDIO_D3{slash}DCMI_D4{slash}USART3_RX{slash}I2S3ext_SD{slash}EVENTOUT-Pad52)") (class "Default")
      (node (ref "U1") (pin "52") (pinfunction "PC11/UART4_RX/SPI3_MISO/SDIO_D3/DCMI_D4/USART3_RX/I2S3ext_SD/EVENTOUT_52") (pintype "bidirectional"))
    )
    (net (code "76") (name "unconnected-(U1B-PC12{slash}UART5_TX{slash}SDIO_CK{slash}DCMI_D9{slash}SPI3_MOSI{slash}I2S3_SD{slash}USART3_CK{slash}EVENTOUT-Pad53)") (class "Default")
      (node (ref "U1") (pin "53") (pinfunction "PC12/UART5_TX/SDIO_CK/DCMI_D9/SPI3_MOSI/I2S3_SD/USART3_CK/EVENTOUT_53") (pintype "bidirectional"))
    )
    (net (code "77") (name "unconnected-(U1B-PC13{slash}EVENTOUT{slash}RTC_AF1-Pad2)") (class "Default")
      (node (ref "U1") (pin "2") (pinfunction "PC13/EVENTOUT/RTC_AF1_2") (pintype "bidirectional"))
    )
    (net (code "78") (name "unconnected-(U4-SCL-Pad7)") (class "Default")
      (node (ref "U4") (pin "7") (pinfunction "SCL_7") (pintype "passive"))
    )
    (net (code "79") (name "unconnected-(U4-SDA-Pad6)") (class "Default")
      (node (ref "U4") (pin "6") (pinfunction "SDA_6") (pintype "passive"))
    )
    (net (code "80") (name "unconnected-(U5-IRD-Pad5)") (class "Default")
      (node (ref "U5") (pin "5") (pinfunction "IRD_5") (pintype "passive"))
    )
    (net (code "81") (name "unconnected-(U5-RD-Pad6)") (class "Default")
      (node (ref "U5") (pin "6") (pinfunction "RD_6") (pintype "passive"))
    )
    (net (code "82") (name "unconnected-(U6-DBGSCL-Pad7)") (class "Default")
      (node (ref "U6") (pin "7") (pinfunction "DBGSCL_7") (pintype "passive"))
    )
    (net (code "83") (name "unconnected-(U6-DBGSDA-Pad8)") (class "Default")
      (node (ref "U6") (pin "8") (pinfunction "DBGSDA_8") (pintype "passive"))
    )
    (net (code "84") (name "unconnected-(U6-NC-Pad5)") (class "Default")
      (node (ref "U6") (pin "5") (pinfunction "NC_5") (pintype "passive"))
    )
    (net (code "85") (name "unconnected-(U6-NC-Pad6)") (class "Default")
      (node (ref "U6") (pin "6") (pinfunction "NC_6") (pintype "passive"))
    )
    (net (code "86") (name "unconnected-(U6-NC-Pad10)") (class "Default")
      (node (ref "U6") (pin "10") (pinfunction "NC_10") (pintype "passive"))
    )
    (net (code "87") (name "unconnected-(U6-NC-Pad16)") (class "Default")
      (node (ref "U6") (pin "16") (pinfunction "NC_16") (pintype "passive"))
    )
    (net (code "88") (name "unconnected-(U6-NC-Pad17)") (class "Default")
      (node (ref "U6") (pin "17") (pinfunction "NC_17") (pintype "passive"))
    )
    (net (code "89") (name "unconnected-(U6-NC-Pad18)") (class "Default")
      (node (ref "U6") (pin "18") (pinfunction "NC_18") (pintype "passive"))
    )
    (net (code "90") (name "unconnected-(U6-NC-Pad19)") (class "Default")
      (node (ref "U6") (pin "19") (pinfunction "NC_19") (pintype "passive"))
    )
    (net (code "91") (name "unconnected-(U6-P00-Pad34)") (class "Default")
      (node (ref "U6") (pin "34") (pinfunction "P00_34") (pintype "passive"))
    )
    (net (code "92") (name "unconnected-(U6-P01-Pad33)") (class "Default")
      (node (ref "U6") (pin "33") (pinfunction "P01_33") (pintype "passive"))
    )
    (net (code "93") (name "unconnected-(U6-P02-Pad32)") (class "Default")
      (node (ref "U6") (pin "32") (pinfunction "P02_32") (pintype "passive"))
    )
    (net (code "94") (name "unconnected-(U6-P03-Pad31)") (class "Default")
      (node (ref "U6") (pin "31") (pinfunction "P03_31") (pintype "passive"))
    )
    (net (code "95") (name "unconnected-(U6-P04-Pad30)") (class "Default")
      (node (ref "U6") (pin "30") (pinfunction "P04_30") (pintype "passive"))
    )
    (net (code "96") (name "unconnected-(U6-P05-Pad29)") (class "Default")
      (node (ref "U6") (pin "29") (pinfunction "P05_29") (pintype "passive"))
    )
    (net (code "97") (name "unconnected-(U6-P07-Pad27)") (class "Default")
      (node (ref "U6") (pin "27") (pinfunction "P07_27") (pintype "passive"))
    )
    (net (code "98") (name "unconnected-(U6-P10-Pad26)") (class "Default")
      (node (ref "U6") (pin "26") (pinfunction "P10_26") (pintype "passive"))
    )
    (net (code "99") (name "unconnected-(U6-P20-Pad9)") (class "Default")
      (node (ref "U6") (pin "9") (pinfunction "P20_9") (pintype "passive"))
    )
    (net (code "100") (name "unconnected-(U6-SCL-Pad20)") (class "Default")
      (node (ref "U6") (pin "20") (pinfunction "SCL_20") (pintype "passive"))
    )
    (net (code "101") (name "unconnected-(U6-SDA-Pad15)") (class "Default")
      (node (ref "U6") (pin "15") (pinfunction "SDA_15") (pintype "passive"))
    )
    (net (code "102") (name "unconnected-(U6-UART_CTS-Pad3)") (class "Default")
      (node (ref "U6") (pin "3") (pinfunction "UART_CTS_3") (pintype "passive"))
    )
    (net (code "103") (name "unconnected-(U6-UART_RTS-Pad4)") (class "Default")
      (node (ref "U6") (pin "4") (pinfunction "UART_RTS_4") (pintype "passive"))
    )
  )
)
